# SparkFun_Mic-Preamp-v12.net
KiCad netlist of a schematic drawn in EAGLE
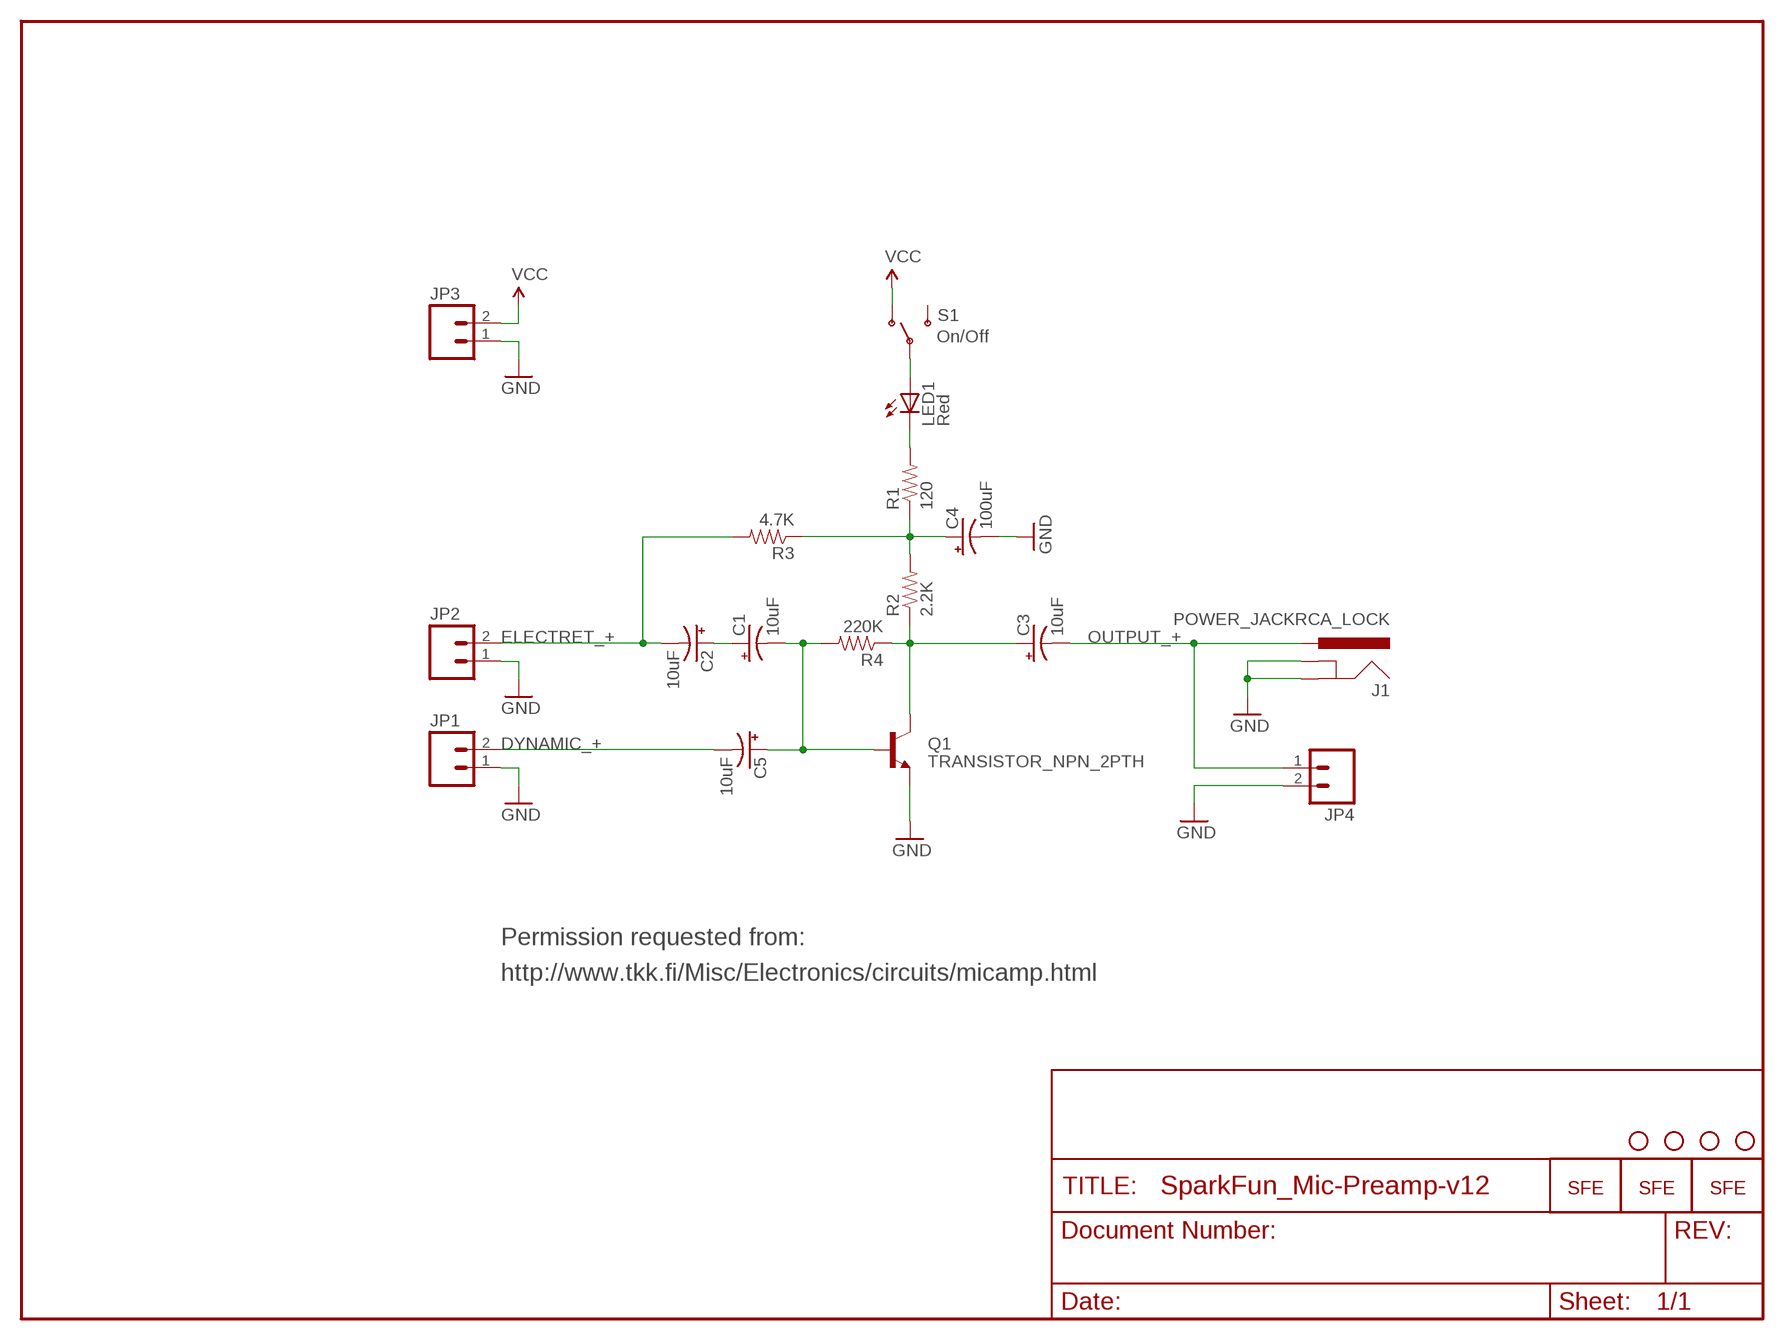
[diagram p0: schematic, sheet 1]

(export (version "E")
  (design (tool "Eeschema 10.0.6"))
  (components
    (comp (ref "C1")
      (value "10uF")
      (footprint "eagle-import:CPOL-RADIAL-10UF-25V")
      (libsource (lib "eagle-import") (part "CAP_POLPTH2"))
    )
    (comp (ref "C2")
      (value "10uF")
      (footprint "eagle-import:CPOL-RADIAL-10UF-25V")
      (libsource (lib "eagle-import") (part "CAP_POLPTH2"))
    )
    (comp (ref "C3")
      (value "10uF")
      (footprint "eagle-import:CPOL-RADIAL-10UF-25V")
      (libsource (lib "eagle-import") (part "CAP_POLPTH2"))
    )
    (comp (ref "C4")
      (value "100uF")
      (footprint "eagle-import:CPOL-RADIAL-100UF-25V")
      (libsource (lib "eagle-import") (part "CAP_POLPTH1"))
    )
    (comp (ref "C5")
      (value "10uF")
      (footprint "eagle-import:CPOL-RADIAL-10UF-25V")
      (libsource (lib "eagle-import") (part "CAP_POLPTH2"))
    )
    (comp (ref "J1")
      (value "POWER_JACKRCA_LOCK")
      (footprint "eagle-import:RCA_LOCK")
      (libsource (lib "eagle-import") (part "POWER_JACKRCA_LOCK"))
    )
    (comp (ref "JP1")
      (value "M02PTH")
      (footprint "eagle-import:1X02")
      (libsource (lib "eagle-import") (part "M02PTH"))
    )
    (comp (ref "JP2")
      (value "M02PTH")
      (footprint "eagle-import:1X02")
      (libsource (lib "eagle-import") (part "M02PTH"))
    )
    (comp (ref "JP3")
      (value "M02PTH")
      (footprint "eagle-import:1X02")
      (libsource (lib "eagle-import") (part "M02PTH"))
    )
    (comp (ref "JP4")
      (value "M02PTH")
      (footprint "eagle-import:1X02")
      (libsource (lib "eagle-import") (part "M02PTH"))
    )
    (comp (ref "JP6")
      (value "LOGO-SFENW2")
      (footprint "eagle-import:SFE-NEW-WEB")
      (libsource (lib "eagle-import") (part "LOGO-SFENW2"))
    )
    (comp (ref "LED1")
      (value "Red")
      (footprint "eagle-import:LED5MM")
      (libsource (lib "eagle-import") (part "LED5MM"))
    )
    (comp (ref "Q1")
      (value "TRANSISTOR_NPN_2PTH")
      (footprint "eagle-import:TO-92")
      (libsource (lib "eagle-import") (part "TRANSISTOR_NPN_2PTH"))
    )
    (comp (ref "R1")
      (value "120")
      (footprint "eagle-import:AXIAL-0.3")
      (libsource (lib "eagle-import") (part "RESISTORPTH1"))
    )
    (comp (ref "R2")
      (value "2.2K")
      (footprint "eagle-import:AXIAL-0.3")
      (libsource (lib "eagle-import") (part "RESISTORPTH1"))
    )
    (comp (ref "R3")
      (value "4.7K")
      (footprint "eagle-import:AXIAL-0.3")
      (libsource (lib "eagle-import") (part "RESISTORPTH1"))
    )
    (comp (ref "R4")
      (value "220K")
      (footprint "eagle-import:AXIAL-0.3")
      (libsource (lib "eagle-import") (part "RESISTORPTH1"))
    )
    (comp (ref "S1")
      (value "On/Off")
      (footprint "eagle-import:SWITCH-SPDT_LOCK.007S")
      (libsource (lib "eagle-import") (part "SWITCH-SPSTPTH_LOCK"))
    )
    (comp (ref "U$1")
      (value "LOGO-SFESK")
      (footprint "eagle-import:SFE-LOGO-FLAME")
      (libsource (lib "eagle-import") (part "LOGO-SFESK"))
    )
    (comp (ref "U$2")
      (value "STAND-OFF")
      (footprint "eagle-import:STAND-OFF")
      (libsource (lib "eagle-import") (part "STAND-OFF"))
    )
    (comp (ref "U$3")
      (value "STAND-OFF")
      (footprint "eagle-import:STAND-OFF")
      (libsource (lib "eagle-import") (part "STAND-OFF"))
    )
    (comp (ref "U$4")
      (value "STAND-OFF")
      (footprint "eagle-import:STAND-OFF")
      (libsource (lib "eagle-import") (part "STAND-OFF"))
    )
    (comp (ref "U$5")
      (value "STAND-OFF")
      (footprint "eagle-import:STAND-OFF")
      (libsource (lib "eagle-import") (part "STAND-OFF"))
    )
    (comp (ref "U$6")
      (value "LOGO-SFESK")
      (footprint "eagle-import:SFE-LOGO-FLAME")
      (libsource (lib "eagle-import") (part "LOGO-SFESK"))
    )
  )
  (nets
    (net (code "1") (name "/DYNAMIC_+") (class "Default")
      (node (ref "C5") (pin "2") (pinfunction "-_2") (pintype "passive"))
      (node (ref "JP1") (pin "2") (pinfunction "2_2") (pintype "passive"))
    )
    (net (code "2") (name "/ELECTRET_+") (class "Default")
      (node (ref "C2") (pin "2") (pinfunction "-_2") (pintype "passive"))
      (node (ref "JP2") (pin "2") (pinfunction "2_2") (pintype "passive"))
      (node (ref "R3") (pin "P$2") (pinfunction "2_P$2") (pintype "passive"))
    )
    (net (code "3") (name "/OUTPUT_+") (class "Default")
      (node (ref "C3") (pin "2") (pinfunction "-_2") (pintype "passive"))
      (node (ref "J1") (pin "BREAK") (pinfunction "PWR_BREAK") (pintype "bidirectional"))
      (node (ref "JP4") (pin "1") (pinfunction "1_1") (pintype "passive"))
    )
    (net (code "4") (name "GND") (class "Default")
      (node (ref "C4") (pin "2") (pinfunction "-_2") (pintype "passive"))
      (node (ref "J1") (pin "BARREL") (pinfunction "GND_BARREL") (pintype "bidirectional"))
      (node (ref "J1") (pin "SPRING") (pinfunction "GNDBREAK_SPRING") (pintype "bidirectional"))
      (node (ref "JP1") (pin "1") (pinfunction "1_1") (pintype "passive"))
      (node (ref "JP2") (pin "1") (pinfunction "1_1") (pintype "passive"))
      (node (ref "JP3") (pin "1") (pinfunction "1_1") (pintype "passive"))
      (node (ref "JP4") (pin "2") (pinfunction "2_2") (pintype "passive"))
      (node (ref "Q1") (pin "3") (pinfunction "E_3") (pintype "passive"))
    )
    (net (code "5") (name "Net-(C1-+)") (class "Default")
      (node (ref "C1") (pin "1") (pinfunction "+_1") (pintype "passive"))
      (node (ref "C2") (pin "1") (pinfunction "+_1") (pintype "passive"))
    )
    (net (code "6") (name "Net-(C1--)") (class "Default")
      (node (ref "C1") (pin "2") (pinfunction "-_2") (pintype "passive"))
      (node (ref "C5") (pin "1") (pinfunction "+_1") (pintype "passive"))
      (node (ref "Q1") (pin "2") (pinfunction "B_2") (pintype "passive"))
      (node (ref "R4") (pin "P$2") (pinfunction "2_P$2") (pintype "passive"))
    )
    (net (code "7") (name "Net-(C3-+)") (class "Default")
      (node (ref "C3") (pin "1") (pinfunction "+_1") (pintype "passive"))
      (node (ref "Q1") (pin "1") (pinfunction "C_1") (pintype "passive"))
      (node (ref "R2") (pin "P$1") (pinfunction "1_P$1") (pintype "passive"))
      (node (ref "R4") (pin "P$1") (pinfunction "1_P$1") (pintype "passive"))
    )
    (net (code "8") (name "Net-(C4-+)") (class "Default")
      (node (ref "C4") (pin "1") (pinfunction "+_1") (pintype "passive"))
      (node (ref "R1") (pin "P$1") (pinfunction "1_P$1") (pintype "passive"))
      (node (ref "R2") (pin "P$2") (pinfunction "2_P$2") (pintype "passive"))
      (node (ref "R3") (pin "P$1") (pinfunction "1_P$1") (pintype "passive"))
    )
    (net (code "9") (name "Net-(LED1-C)") (class "Default")
      (node (ref "LED1") (pin "K") (pinfunction "C_K") (pintype "passive"))
      (node (ref "R1") (pin "P$2") (pinfunction "2_P$2") (pintype "passive"))
    )
    (net (code "10") (name "Net-(S1-P)") (class "Default")
      (node (ref "LED1") (pin "A") (pinfunction "A_A") (pintype "passive"))
      (node (ref "S1") (pin "2") (pinfunction "P_2") (pintype "passive"))
    )
    (net (code "11") (name "VCC") (class "Default")
      (node (ref "JP3") (pin "2") (pinfunction "2_2") (pintype "passive"))
      (node (ref "S1") (pin "1") (pinfunction "O_1") (pintype "passive"))
    )
    (net (code "12") (name "unconnected-(S1-S-Pad3)") (class "Default")
      (node (ref "S1") (pin "3") (pinfunction "S_3") (pintype "passive"))
    )
  )
)
